# ePaper_1_54_v1_0_1.net
KiCad netlist of a schematic drawn in EAGLE
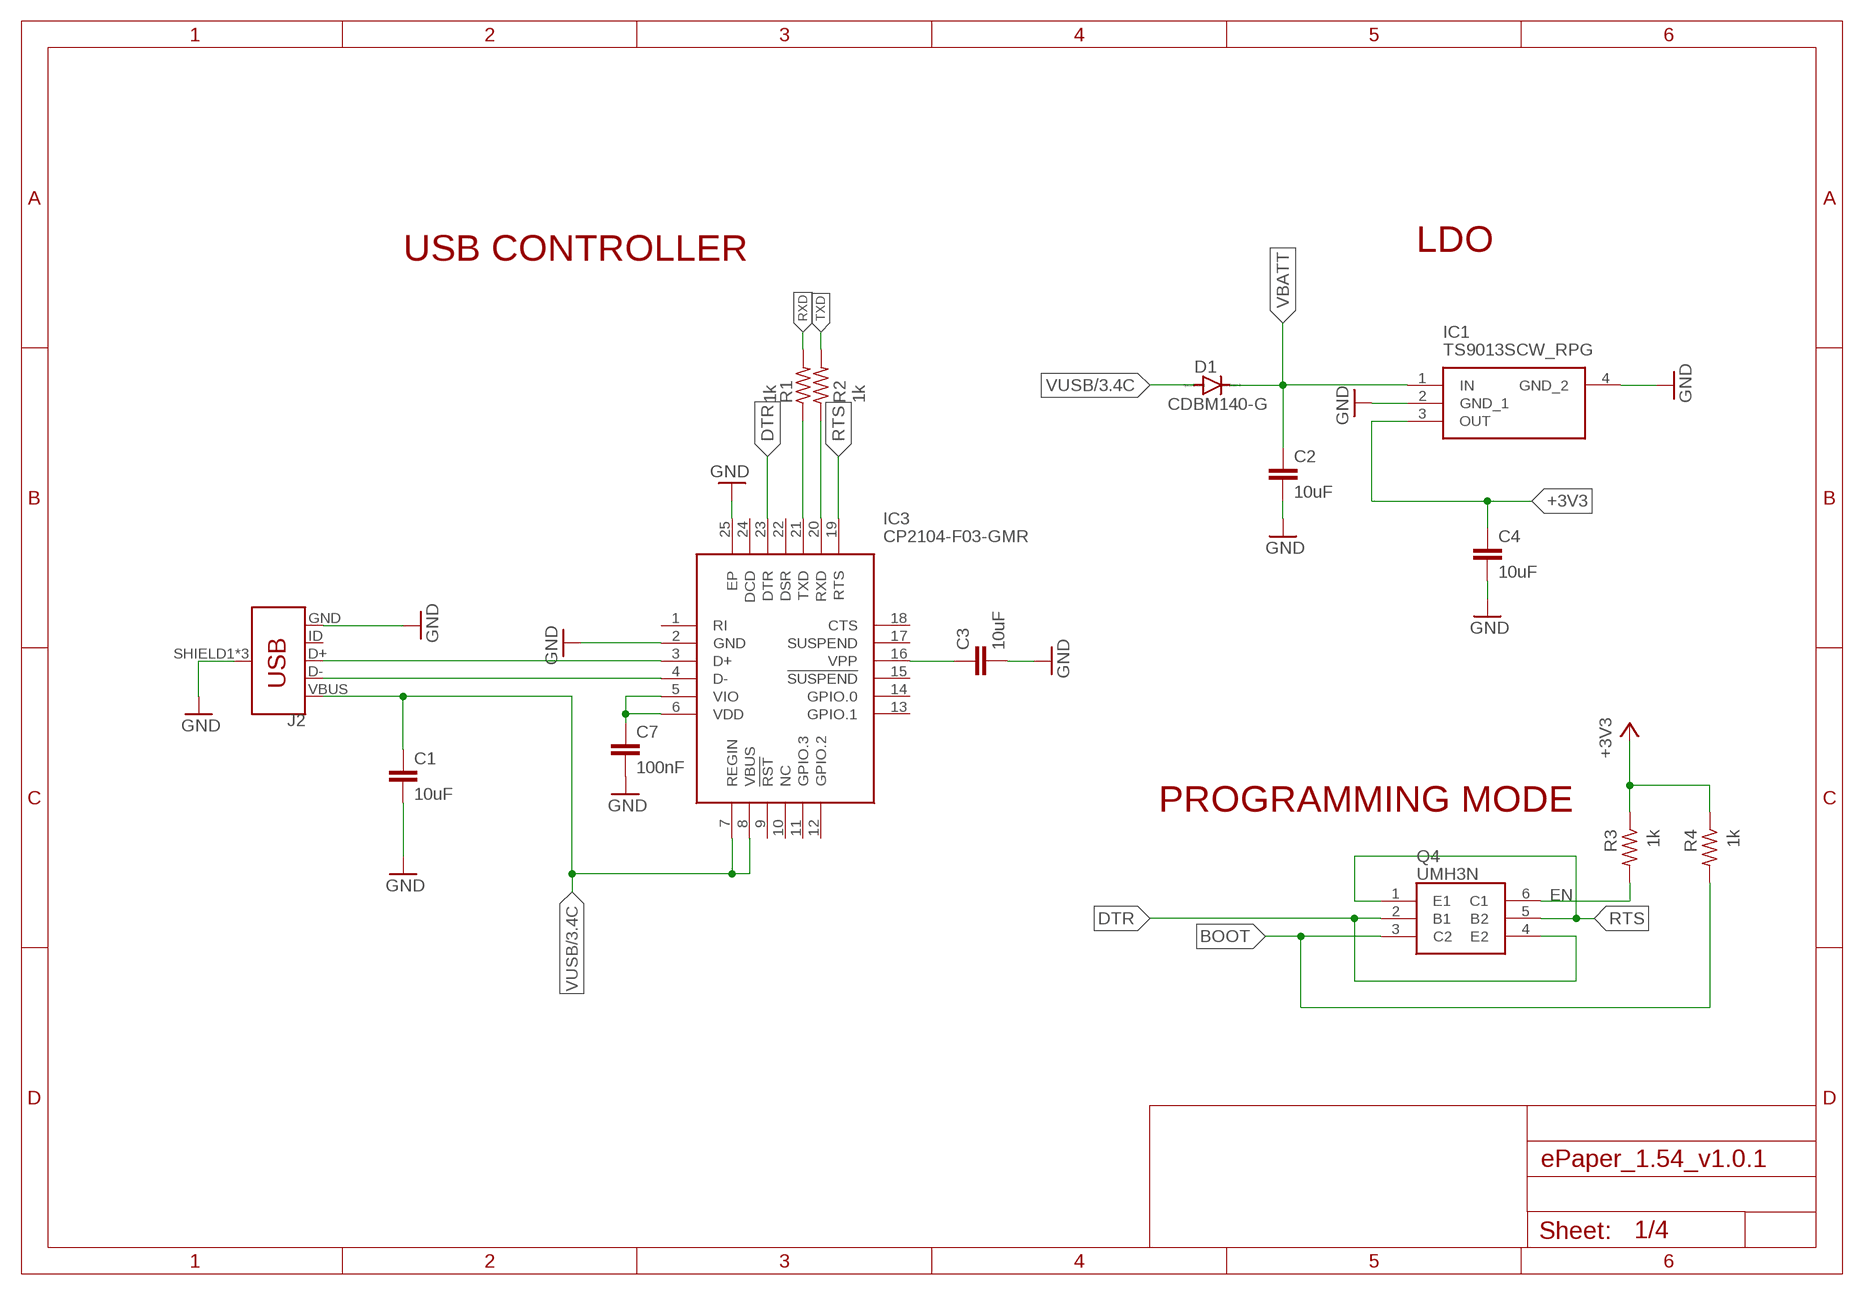
[diagram p0: schematic, sheet 1]
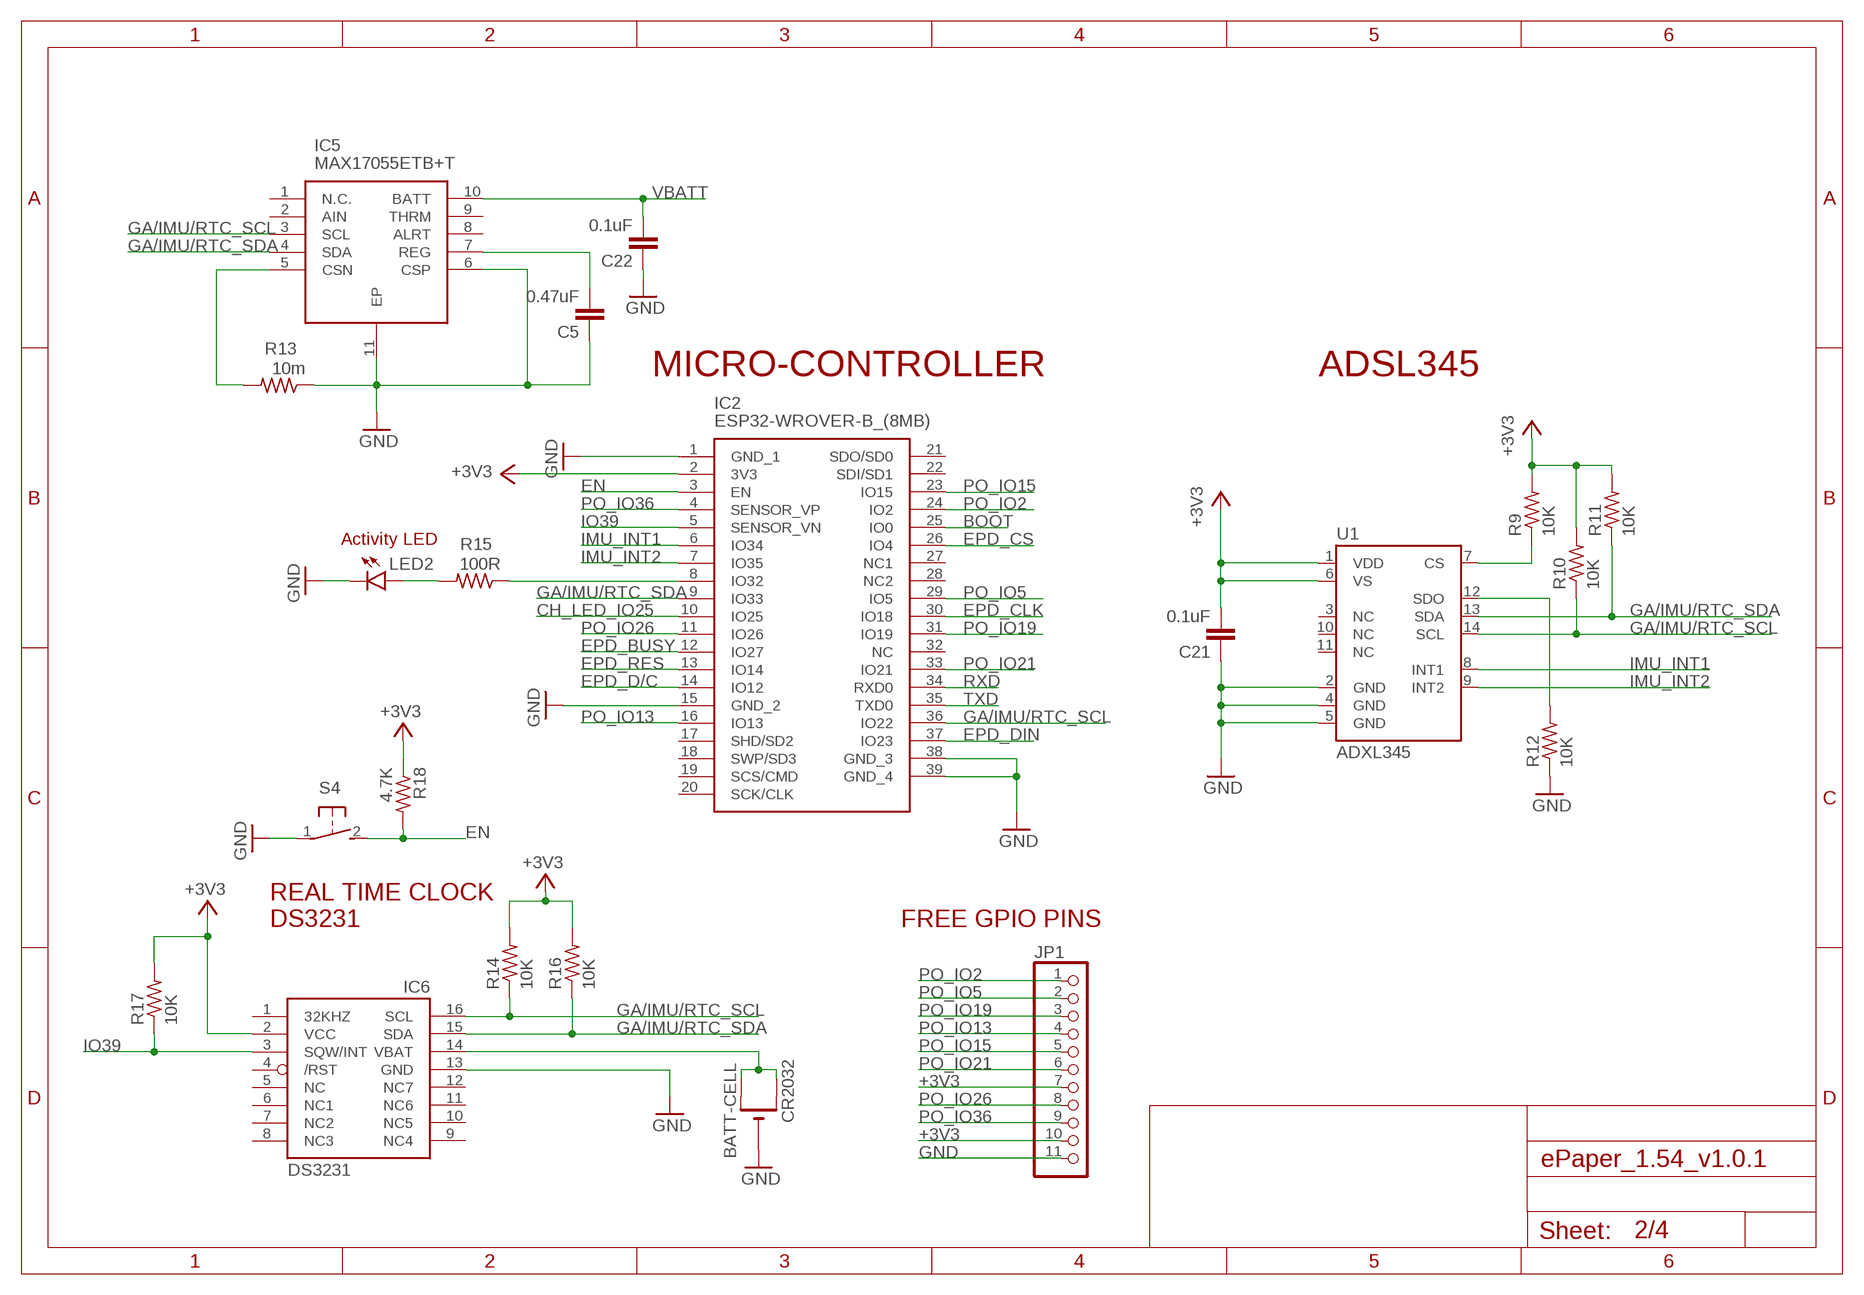
[diagram p1: schematic, sheet 2]
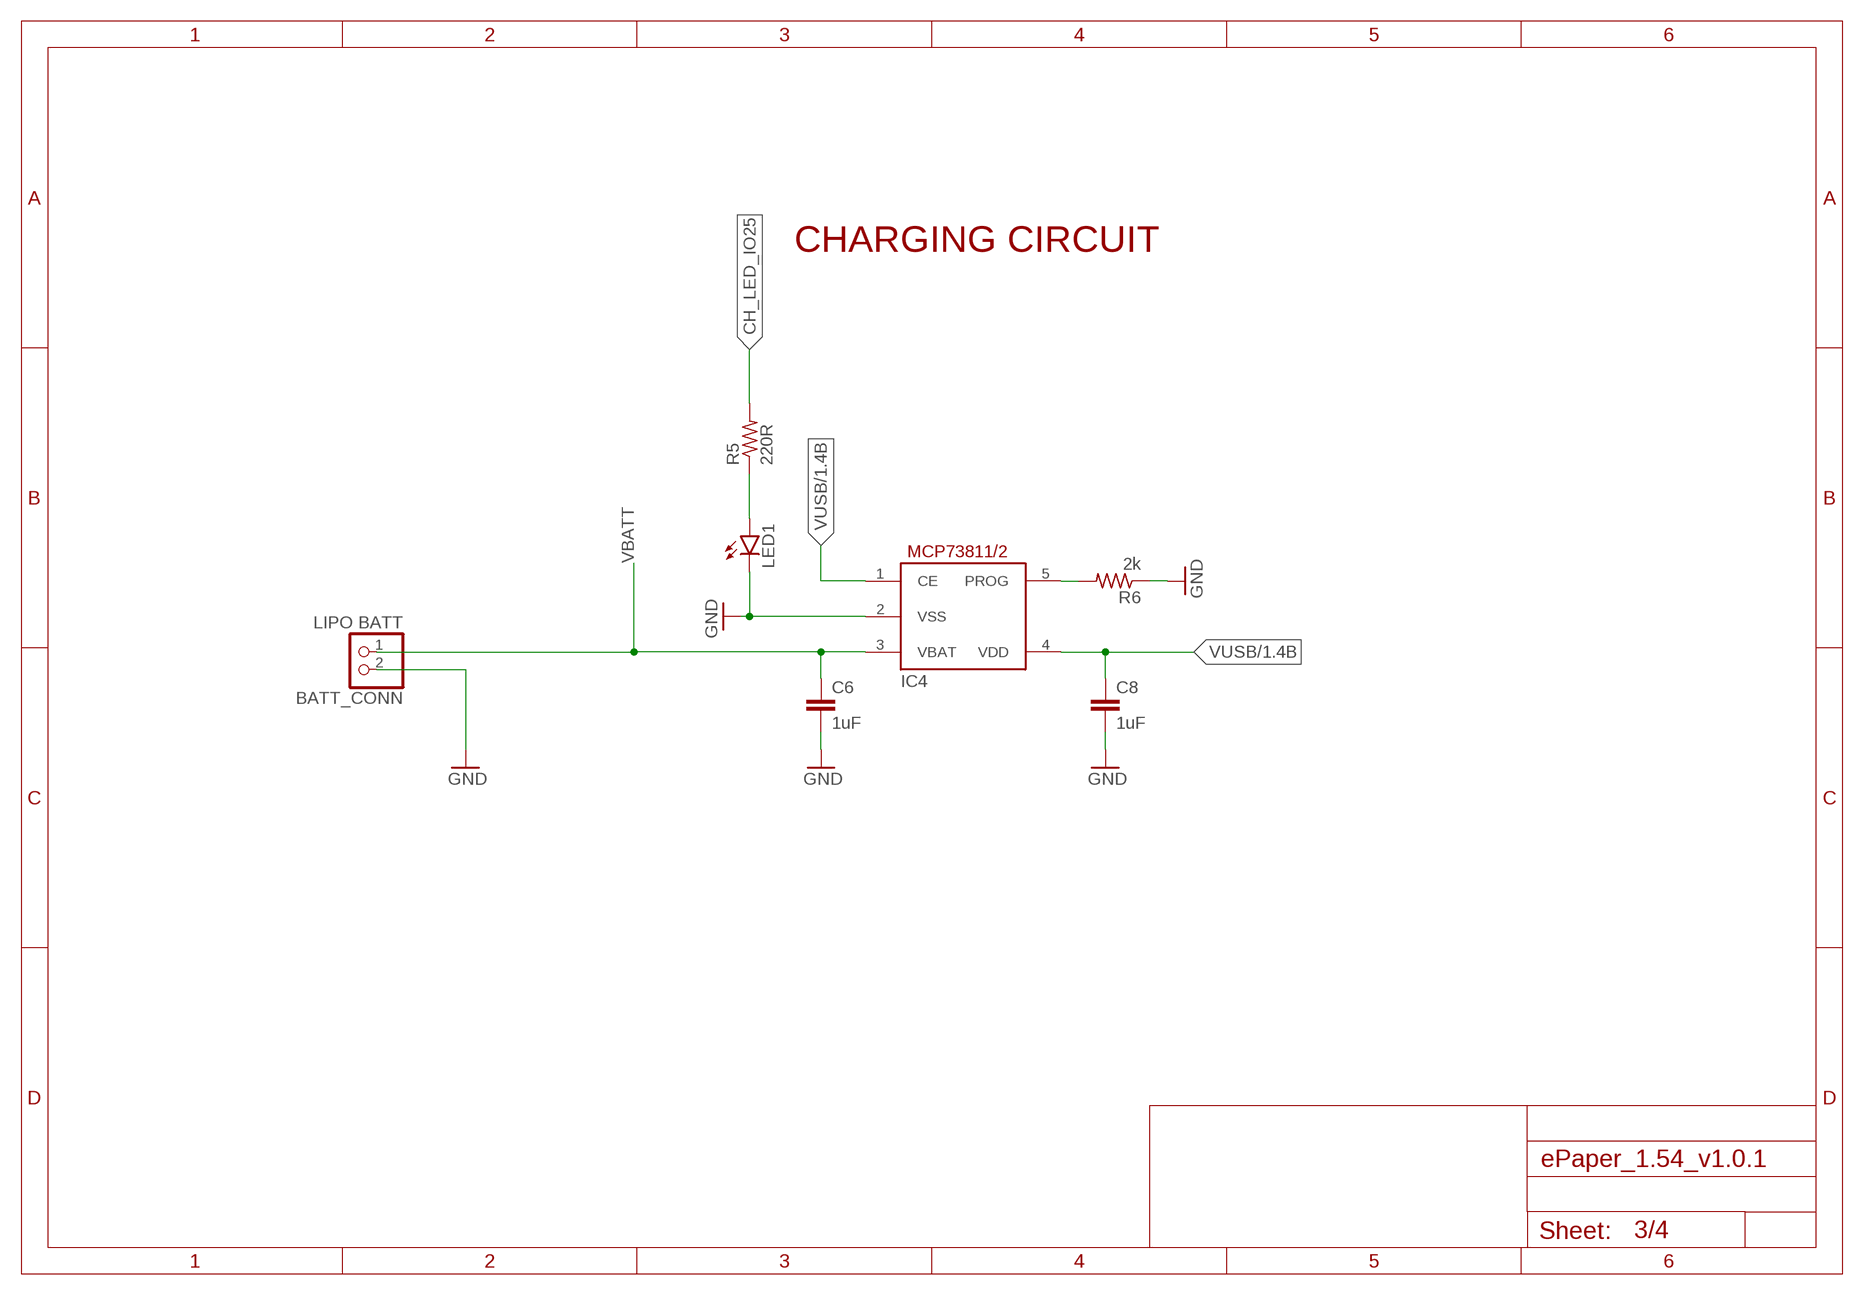
[diagram p2: schematic, sheet 3]
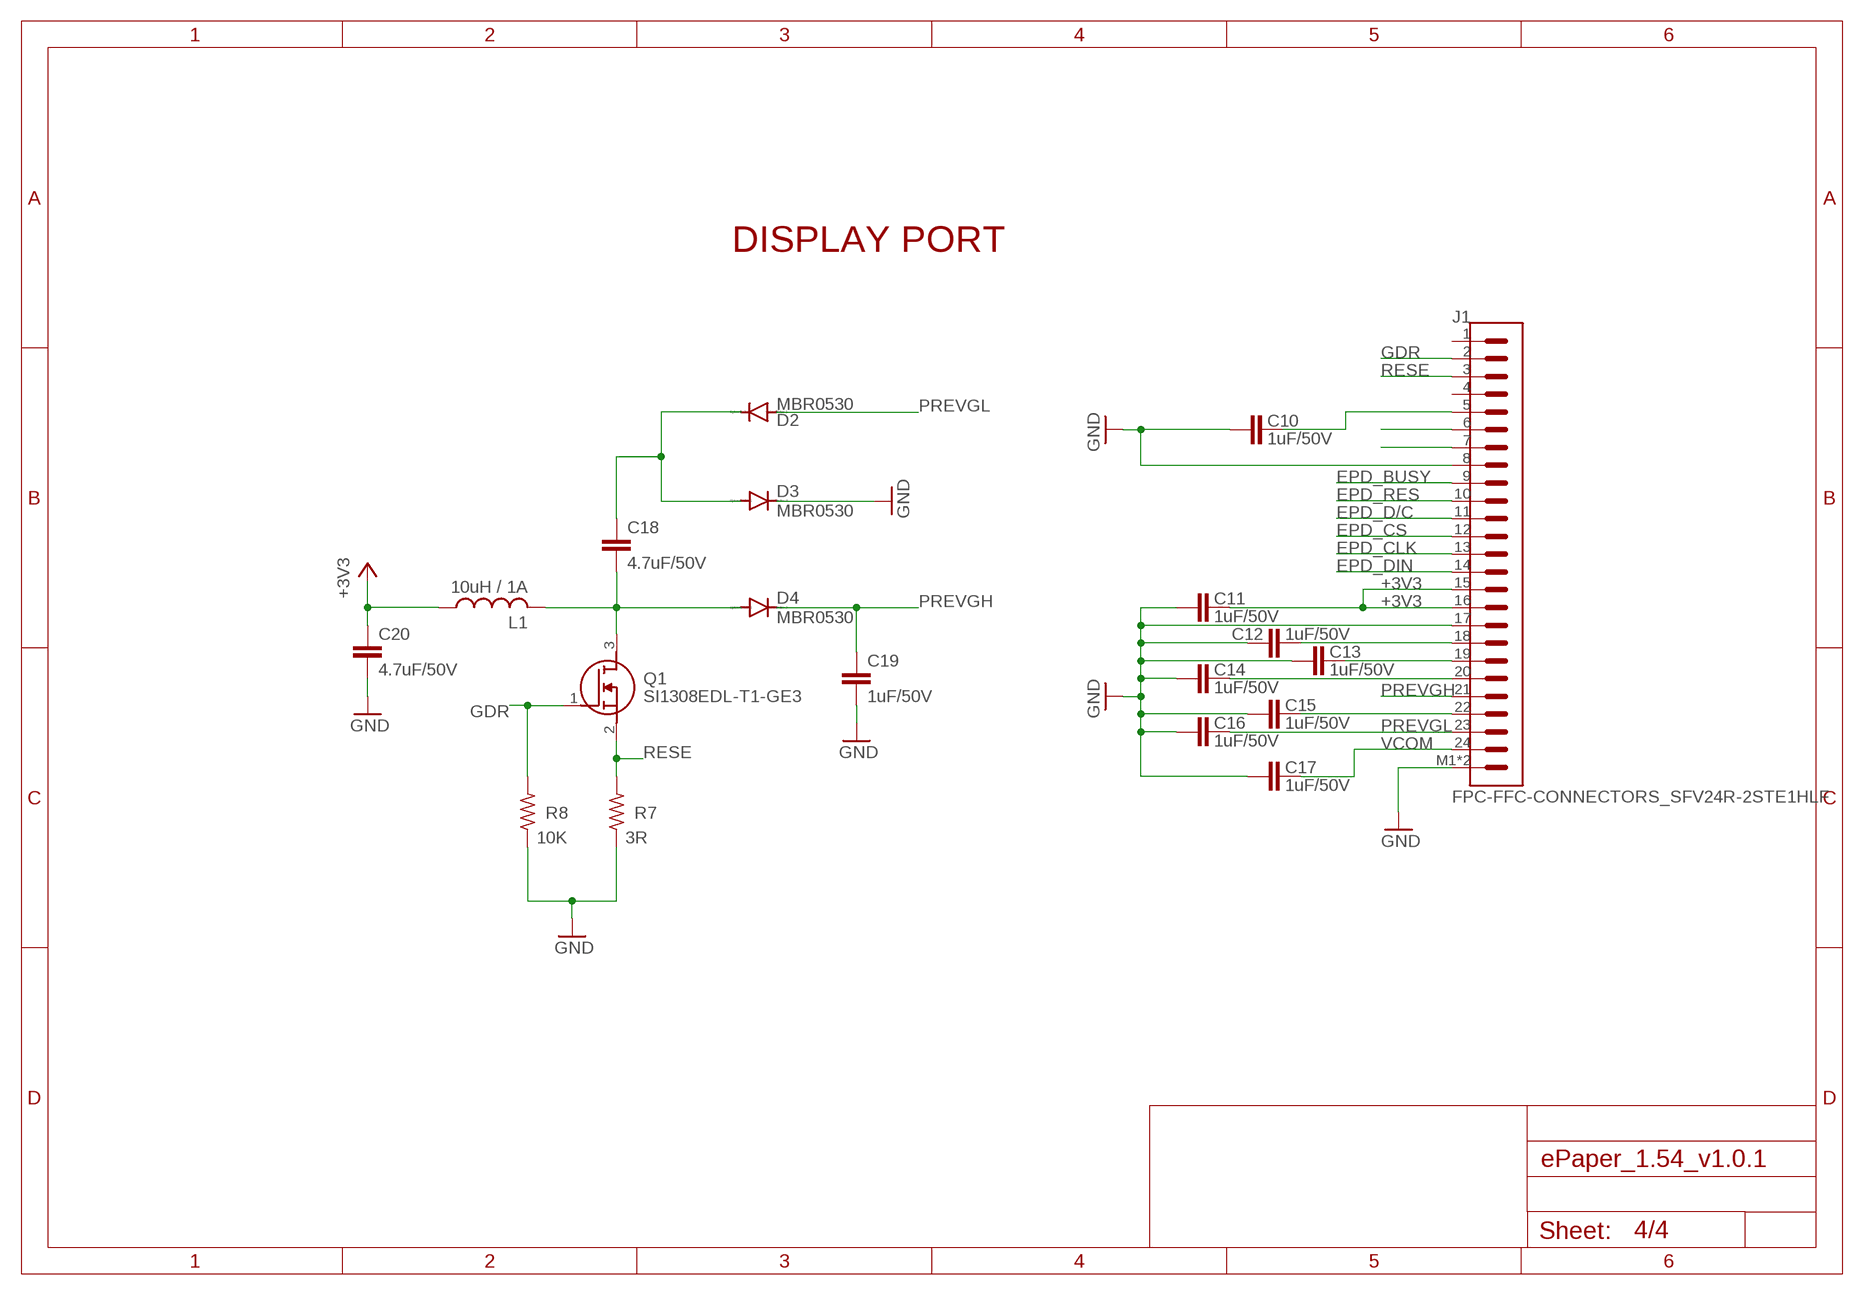
[diagram p3: schematic, sheet 4]

(export (version "E")
  (design (tool "Eeschema 10.0.6"))
  (components
    (comp (ref "BATT_CONN")
      (value "LIPO BATT")
      (footprint "eagle-import:JST-PH-2-THM-RA")
      (libsource (lib "eagle-import") (part "JST_2PIN-THM-RA"))
    )
    (comp (ref "C6")
      (value "1uF")
      (footprint "eagle-import:C0805")
      (libsource (lib "eagle-import") (part "C-EUC0805"))
    )
    (comp (ref "C8")
      (value "1uF")
      (footprint "eagle-import:C0805")
      (libsource (lib "eagle-import") (part "C-EUC0805"))
    )
    (comp (ref "IC4")
      (value "MCP73811/2")
      (footprint "eagle-import:SOT23-5L")
      (libsource (lib "eagle-import") (part "MCP73811/2"))
    )
    (comp (ref "LED1")
      (value "LEDCHIPLED_0805")
      (footprint "eagle-import:CHIPLED_0805")
      (libsource (lib "eagle-import") (part "LEDCHIPLED_0805"))
    )
    (comp (ref "R5")
      (value "220R")
      (footprint "eagle-import:R0603")
      (libsource (lib "eagle-import") (part "R-US_R0603"))
    )
    (comp (ref "R6")
      (value "2k")
      (footprint "eagle-import:R0603")
      (libsource (lib "eagle-import") (part "R-US_R0603"))
    )
    (comp (ref "C1")
      (value "10uF")
      (footprint "eagle-import:C0603")
      (libsource (lib "eagle-import") (part "C-EUC0603"))
    )
    (comp (ref "C2")
      (value "10uF")
      (footprint "eagle-import:C0603")
      (libsource (lib "eagle-import") (part "C-EUC0603"))
    )
    (comp (ref "C3")
      (value "10uF")
      (footprint "eagle-import:C0603")
      (libsource (lib "eagle-import") (part "C-EUC0603"))
    )
    (comp (ref "C4")
      (value "10uF")
      (footprint "eagle-import:C0603")
      (libsource (lib "eagle-import") (part "C-EUC0603"))
    )
    (comp (ref "C7")
      (value "100nF")
      (footprint "eagle-import:C0603")
      (libsource (lib "eagle-import") (part "C-EUC0603"))
    )
    (comp (ref "D1")
      (value "CDBM140-G")
      (footprint "eagle-import:SOD123")
      (libsource (lib "eagle-import") (part "DIODE-SOD123"))
    )
    (comp (ref "IC1")
      (value "TS9013SCW_RPG")
      (footprint "eagle-import:SOT230P700X180-4N")
      (fields (field (name "MANUFACTURER_PART_NUMBER") "TS9013SCW RPG"))
      (libsource (lib "eagle-import") (part "TS9013SCW_RPG"))
    )
    (comp (ref "IC3")
      (value "CP2104-F03-GMR")
      (footprint "eagle-import:QFN50P400X400X80-25N")
      (fields (field (name "MOUSER_PART_NUMBER") "634-CP2104-F03-GMR"))
      (libsource (lib "eagle-import") (part "CP2104-F03-GMR"))
    )
    (comp (ref "J2")
      (value "USB_MICRO-B_FEMALE-SMT")
      (footprint "eagle-import:USB-B-MICRO-SMD")
      (libsource (lib "eagle-import") (part "USB_MICRO-B_FEMALE-SMT"))
    )
    (comp (ref "Q4")
      (value "UMH3N")
      (footprint "eagle-import:SOT65P230X110-6N")
      (libsource (lib "eagle-import") (part "UMH3N"))
    )
    (comp (ref "R1")
      (value "1k")
      (footprint "eagle-import:R0603")
      (libsource (lib "eagle-import") (part "R-US_R0603"))
    )
    (comp (ref "R2")
      (value "1k")
      (footprint "eagle-import:R0603")
      (libsource (lib "eagle-import") (part "R-US_R0603"))
    )
    (comp (ref "R3")
      (value "1k")
      (footprint "eagle-import:R0603")
      (libsource (lib "eagle-import") (part "R-US_R0603"))
    )
    (comp (ref "R4")
      (value "1k")
      (footprint "eagle-import:R0603")
      (libsource (lib "eagle-import") (part "R-US_R0603"))
    )
    (comp (ref "C10")
      (value "1uF/50V")
      (footprint "eagle-import:C0805")
      (libsource (lib "eagle-import") (part "C-EUC0805"))
    )
    (comp (ref "C11")
      (value "1uF/50V")
      (footprint "eagle-import:C0805")
      (libsource (lib "eagle-import") (part "C-EUC0805"))
    )
    (comp (ref "C12")
      (value "1uF/50V")
      (footprint "eagle-import:C0805")
      (libsource (lib "eagle-import") (part "C-EUC0805"))
    )
    (comp (ref "C13")
      (value "1uF/50V")
      (footprint "eagle-import:C0805")
      (libsource (lib "eagle-import") (part "C-EUC0805"))
    )
    (comp (ref "C14")
      (value "1uF/50V")
      (footprint "eagle-import:C0805")
      (libsource (lib "eagle-import") (part "C-EUC0805"))
    )
    (comp (ref "C15")
      (value "1uF/50V")
      (footprint "eagle-import:C0805")
      (libsource (lib "eagle-import") (part "C-EUC0805"))
    )
    (comp (ref "C16")
      (value "1uF/50V")
      (footprint "eagle-import:C0805")
      (libsource (lib "eagle-import") (part "C-EUC0805"))
    )
    (comp (ref "C17")
      (value "1uF/50V")
      (footprint "eagle-import:C0805")
      (libsource (lib "eagle-import") (part "C-EUC0805"))
    )
    (comp (ref "C18")
      (value "4.7uF/50V")
      (footprint "eagle-import:C0805")
      (libsource (lib "eagle-import") (part "C-EUC0805"))
    )
    (comp (ref "C19")
      (value "1uF/50V")
      (footprint "eagle-import:C0805")
      (libsource (lib "eagle-import") (part "C-EUC0805"))
    )
    (comp (ref "C20")
      (value "4.7uF/50V")
      (footprint "eagle-import:C0805")
      (libsource (lib "eagle-import") (part "C-EUC0805"))
    )
    (comp (ref "D2")
      (value "MBR0530")
      (footprint "eagle-import:SOD123")
      (libsource (lib "eagle-import") (part "MBR0520LT"))
    )
    (comp (ref "D3")
      (value "MBR0530")
      (footprint "eagle-import:SOD123")
      (libsource (lib "eagle-import") (part "MBR0520LT"))
    )
    (comp (ref "D4")
      (value "MBR0530")
      (footprint "eagle-import:SOD123")
      (libsource (lib "eagle-import") (part "MBR0520LT"))
    )
    (comp (ref "J1")
      (value "FPC-FFC-CONNECTORS_SFV24R-2STE1HLF")
      (footprint "eagle-import:FPC-FFC-CONNECTORS_SFV24R-2STE1HLF")
      (fields
        (field (name "DIGIKEY_PARTNO") "609-4321-2-ND")
        (field (name "MANUFACTURER") "Amphenol ICC (FCI)")
        (field (name "MPN") "SFV24R-2STE1HLF")
        (field (name "CREATED_BY") "Abrar Ashraf")
      )
      (libsource (lib "eagle-import") (part "FPC-FFC-CONNECTORS_SFV24R-2STE1HLF"))
    )
    (comp (ref "L1")
      (value "10uH / 1A")
      (footprint "eagle-import:L3225P")
      (libsource (lib "eagle-import") (part "L-USL3225P"))
    )
    (comp (ref "Q1")
      (value "SI1308EDL-T1-GE3")
      (footprint "eagle-import:SOT65P210X110-3N")
      (fields
        (field (name "MANUFACTURER_PART_NUMBER") "Si1308EDL-T1-GE3")
        (field (name "MOUSER_PART_NUMBER") "78-SI1308EDL-T1-GE3")
        (field (name "RS_PART_NUMBER") "7879121P")
      )
      (libsource (lib "eagle-import") (part "SI1308EDL-T1-GE3"))
    )
    (comp (ref "R7")
      (value "3R")
      (footprint "eagle-import:R0603")
      (libsource (lib "eagle-import") (part "R-US_R0603"))
    )
    (comp (ref "R8")
      (value "10K")
      (footprint "eagle-import:R0603")
      (libsource (lib "eagle-import") (part "R-US_R0603"))
    )
    (comp (ref "BATT-CELL")
      (value "CR2032")
      (footprint "eagle-import:CR2032-SMD")
      (libsource (lib "eagle-import") (part "CR2032SMT"))
    )
    (comp (ref "C5")
      (value "0.47uF")
      (footprint "eagle-import:C0603")
      (libsource (lib "eagle-import") (part "C-EUC0603"))
    )
    (comp (ref "C21")
      (value "0.1uF")
      (footprint "eagle-import:C0603")
      (libsource (lib "eagle-import") (part "C-EUC0603"))
    )
    (comp (ref "C22")
      (value "0.1uF")
      (footprint "eagle-import:C0603")
      (libsource (lib "eagle-import") (part "C-EUC0603"))
    )
    (comp (ref "IC2")
      (value "ESP32-WROVER-B_(8MB)")
      (footprint "eagle-import:ESP32WROVERIB8MB")
      (fields
        (field (name "MANUFACTURER_PART_NUMBER") "ESP32-WROVER-B (16MB)")
        (field (name "MOUSER_PART_NUMBER") "356-ESP32-WROB(16MB)")
      )
      (libsource (lib "eagle-import") (part "ESP32-WROVER-B_(8MB)"))
    )
    (comp (ref "IC5")
      (value "MAX17055ETB+T")
      (footprint "eagle-import:SON40P250X200X80-11N")
      (fields
        (field (name "MOUSER_PART_NUMBER") "700-MAX17055ETB+T")
        (field (name "RS_PART_NUMBER") "1913808")
      )
      (libsource (lib "eagle-import") (part "MAX17055ETB+T"))
    )
    (comp (ref "IC6")
      (value "DS3231/SO")
      (footprint "eagle-import:SO16W")
      (libsource (lib "eagle-import") (part "DS3231/SO"))
    )
    (comp (ref "JP1")
      (value "PINHD-1X11_2.54-S")
      (footprint "eagle-import:1X11-S")
      (libsource (lib "eagle-import") (part "PINHD-1X11_2.54-S"))
    )
    (comp (ref "LED2")
      (value "LEDCHIPLED_0805")
      (footprint "eagle-import:CHIPLED_0805")
      (libsource (lib "eagle-import") (part "LEDCHIPLED_0805"))
    )
    (comp (ref "R9")
      (value "10K")
      (footprint "eagle-import:R0603")
      (libsource (lib "eagle-import") (part "R-US_R0603"))
    )
    (comp (ref "R10")
      (value "10K")
      (footprint "eagle-import:R0603")
      (libsource (lib "eagle-import") (part "R-US_R0603"))
    )
    (comp (ref "R11")
      (value "10K")
      (footprint "eagle-import:R0603")
      (libsource (lib "eagle-import") (part "R-US_R0603"))
    )
    (comp (ref "R12")
      (value "10K")
      (footprint "eagle-import:R0603")
      (libsource (lib "eagle-import") (part "R-US_R0603"))
    )
    (comp (ref "R13")
      (value "10m")
      (footprint "eagle-import:R0603")
      (libsource (lib "eagle-import") (part "R-US_R0603"))
    )
    (comp (ref "R14")
      (value "10K")
      (footprint "eagle-import:R0603")
      (libsource (lib "eagle-import") (part "R-US_R0603"))
    )
    (comp (ref "R15")
      (value "100R")
      (footprint "eagle-import:R0603")
      (libsource (lib "eagle-import") (part "R-US_R0603"))
    )
    (comp (ref "R16")
      (value "10K")
      (footprint "eagle-import:R0603")
      (libsource (lib "eagle-import") (part "R-US_R0603"))
    )
    (comp (ref "R17")
      (value "10K")
      (footprint "eagle-import:R0603")
      (libsource (lib "eagle-import") (part "R-US_R0603"))
    )
    (comp (ref "R18")
      (value "4.7K")
      (footprint "eagle-import:R0603")
      (libsource (lib "eagle-import") (part "R-US_R0603"))
    )
    (comp (ref "S4")
      (value "31-XX")
      (footprint "eagle-import:B3F-31XX")
      (fields (field (name "MPN") "B3F-3100"))
      (libsource (lib "eagle-import") (part "31-XX"))
    )
    (comp (ref "U1")
      (value "ADXL345")
      (footprint "eagle-import:LGA14")
      (libsource (lib "eagle-import") (part "ADXL345"))
    )
  )
  (nets
    (net (code "1") (name "+3V3") (class "Default")
      (node (ref "C11") (pin "2") (pinfunction "2_2") (pintype "passive"))
      (node (ref "C20") (pin "2") (pinfunction "2_2") (pintype "passive"))
      (node (ref "C21") (pin "2") (pinfunction "2_2") (pintype "passive"))
      (node (ref "C4") (pin "1") (pinfunction "1_1") (pintype "passive"))
      (node (ref "IC1") (pin "3") (pinfunction "OUT_3") (pintype "output"))
      (node (ref "IC2") (pin "2") (pinfunction "3V3_2") (pintype "bidirectional"))
      (node (ref "IC6") (pin "2") (pinfunction "VCC_2") (pintype "power_in"))
      (node (ref "J1") (pin "15") (pinfunction "15_15") (pintype "passive"))
      (node (ref "J1") (pin "16") (pinfunction "16_16") (pintype "passive"))
      (node (ref "JP1") (pin "10") (pinfunction "10_10") (pintype "passive"))
      (node (ref "JP1") (pin "7") (pinfunction "7_7") (pintype "passive"))
      (node (ref "L1") (pin "1") (pinfunction "1_1") (pintype "passive"))
      (node (ref "R10") (pin "2") (pinfunction "2_2") (pintype "passive"))
      (node (ref "R11") (pin "2") (pinfunction "2_2") (pintype "passive"))
      (node (ref "R14") (pin "2") (pinfunction "2_2") (pintype "passive"))
      (node (ref "R16") (pin "2") (pinfunction "2_2") (pintype "passive"))
      (node (ref "R17") (pin "2") (pinfunction "2_2") (pintype "passive"))
      (node (ref "R18") (pin "1") (pinfunction "1_1") (pintype "passive"))
      (node (ref "R3") (pin "1") (pinfunction "1_1") (pintype "passive"))
      (node (ref "R4") (pin "1") (pinfunction "1_1") (pintype "passive"))
      (node (ref "R9") (pin "2") (pinfunction "2_2") (pintype "passive"))
      (node (ref "U1") (pin "1") (pinfunction "VDD_1") (pintype "bidirectional"))
      (node (ref "U1") (pin "6") (pinfunction "VS_6") (pintype "bidirectional"))
    )
    (net (code "2") (name "BOOT") (class "Default")
      (node (ref "IC2") (pin "25") (pinfunction "IO0_25") (pintype "bidirectional"))
      (node (ref "Q4") (pin "3") (pinfunction "C2_3") (pintype "bidirectional"))
      (node (ref "R4") (pin "2") (pinfunction "2_2") (pintype "passive"))
    )
    (net (code "3") (name "CH_LED_IO25") (class "Default")
      (node (ref "IC2") (pin "10") (pinfunction "IO25_10") (pintype "bidirectional"))
      (node (ref "R5") (pin "2") (pinfunction "2_2") (pintype "passive"))
    )
    (net (code "4") (name "DTR") (class "Default")
      (node (ref "IC3") (pin "23") (pinfunction "DTR_23") (pintype "bidirectional"))
      (node (ref "Q4") (pin "2") (pinfunction "B1_2") (pintype "bidirectional"))
      (node (ref "Q4") (pin "4") (pinfunction "E2_4") (pintype "bidirectional"))
    )
    (net (code "5") (name "EN") (class "Default")
      (node (ref "IC2") (pin "3") (pinfunction "EN_3") (pintype "bidirectional"))
      (node (ref "Q4") (pin "6") (pinfunction "C1_6") (pintype "bidirectional"))
      (node (ref "R18") (pin "2") (pinfunction "2_2") (pintype "passive"))
      (node (ref "R3") (pin "2") (pinfunction "2_2") (pintype "passive"))
      (node (ref "S4") (pin "2") (pinfunction "S_2") (pintype "passive"))
    )
    (net (code "6") (name "EPD_BUSY") (class "Default")
      (node (ref "IC2") (pin "12") (pinfunction "IO27_12") (pintype "bidirectional"))
      (node (ref "J1") (pin "9") (pinfunction "9_9") (pintype "passive"))
    )
    (net (code "7") (name "EPD_CLK") (class "Default")
      (node (ref "IC2") (pin "30") (pinfunction "IO18_30") (pintype "bidirectional"))
      (node (ref "J1") (pin "13") (pinfunction "13_13") (pintype "passive"))
    )
    (net (code "8") (name "EPD_CS") (class "Default")
      (node (ref "IC2") (pin "26") (pinfunction "IO4_26") (pintype "bidirectional"))
      (node (ref "J1") (pin "12") (pinfunction "12_12") (pintype "passive"))
    )
    (net (code "9") (name "EPD_DIN") (class "Default")
      (node (ref "IC2") (pin "37") (pinfunction "IO23_37") (pintype "bidirectional"))
      (node (ref "J1") (pin "14") (pinfunction "14_14") (pintype "passive"))
    )
    (net (code "10") (name "EPD_D{slash}C") (class "Default")
      (node (ref "IC2") (pin "14") (pinfunction "IO12_14") (pintype "bidirectional"))
      (node (ref "J1") (pin "11") (pinfunction "11_11") (pintype "passive"))
    )
    (net (code "11") (name "EPD_RES") (class "Default")
      (node (ref "IC2") (pin "13") (pinfunction "IO14_13") (pintype "bidirectional"))
      (node (ref "J1") (pin "10") (pinfunction "10_10") (pintype "passive"))
    )
    (net (code "12") (name "GA{slash}IMU{slash}RTC_SCL") (class "Default")
      (node (ref "IC2") (pin "36") (pinfunction "IO22_36") (pintype "bidirectional"))
      (node (ref "IC5") (pin "3") (pinfunction "SCL_3") (pintype "bidirectional"))
      (node (ref "IC6") (pin "16") (pinfunction "SCL_16") (pintype "bidirectional"))
      (node (ref "R10") (pin "1") (pinfunction "1_1") (pintype "passive"))
      (node (ref "R14") (pin "1") (pinfunction "1_1") (pintype "passive"))
      (node (ref "U1") (pin "14") (pinfunction "SCL_14") (pintype "bidirectional"))
    )
    (net (code "13") (name "GA{slash}IMU{slash}RTC_SDA") (class "Default")
      (node (ref "IC2") (pin "9") (pinfunction "IO33_9") (pintype "bidirectional"))
      (node (ref "IC5") (pin "4") (pinfunction "SDA_4") (pintype "bidirectional"))
      (node (ref "IC6") (pin "15") (pinfunction "SDA_15") (pintype "bidirectional"))
      (node (ref "R11") (pin "1") (pinfunction "1_1") (pintype "passive"))
      (node (ref "R16") (pin "1") (pinfunction "1_1") (pintype "passive"))
      (node (ref "U1") (pin "13") (pinfunction "SDA_13") (pintype "bidirectional"))
    )
    (net (code "14") (name "GDR") (class "Default")
      (node (ref "J1") (pin "2") (pinfunction "2_2") (pintype "passive"))
      (node (ref "Q1") (pin "1") (pinfunction "G_1") (pintype "input"))
      (node (ref "R8") (pin "2") (pinfunction "2_2") (pintype "passive"))
    )
    (net (code "15") (name "GND") (class "Default")
      (node (ref "BATT-CELL") (pin "-") (pinfunction "-_-") (pintype "passive"))
      (node (ref "BATT_CONN") (pin "2") (pinfunction "1_2") (pintype "passive"))
      (node (ref "C1") (pin "2") (pinfunction "2_2") (pintype "passive"))
      (node (ref "C10") (pin "1") (pinfunction "1_1") (pintype "passive"))
      (node (ref "C11") (pin "1") (pinfunction "1_1") (pintype "passive"))
      (node (ref "C12") (pin "1") (pinfunction "1_1") (pintype "passive"))
      (node (ref "C13") (pin "1") (pinfunction "1_1") (pintype "passive"))
      (node (ref "C14") (pin "1") (pinfunction "1_1") (pintype "passive"))
      (node (ref "C15") (pin "1") (pinfunction "1_1") (pintype "passive"))
      (node (ref "C16") (pin "1") (pinfunction "1_1") (pintype "passive"))
      (node (ref "C17") (pin "1") (pinfunction "1_1") (pintype "passive"))
      (node (ref "C19") (pin "1") (pinfunction "1_1") (pintype "passive"))
      (node (ref "C2") (pin "2") (pinfunction "2_2") (pintype "passive"))
      (node (ref "C20") (pin "1") (pinfunction "1_1") (pintype "passive"))
      (node (ref "C21") (pin "1") (pinfunction "1_1") (pintype "passive"))
      (node (ref "C22") (pin "1") (pinfunction "1_1") (pintype "passive"))
      (node (ref "C3") (pin "2") (pinfunction "2_2") (pintype "passive"))
      (node (ref "C4") (pin "2") (pinfunction "2_2") (pintype "passive"))
      (node (ref "C5") (pin "1") (pinfunction "1_1") (pintype "passive"))
      (node (ref "C6") (pin "2") (pinfunction "2_2") (pintype "passive"))
      (node (ref "C7") (pin "2") (pinfunction "2_2") (pintype "passive"))
      (node (ref "C8") (pin "2") (pinfunction "2_2") (pintype "passive"))
      (node (ref "D3") (pin "C") (pinfunction "C_C") (pintype "passive"))
      (node (ref "IC1") (pin "2") (pinfunction "GND_1_2") (pintype "power_in"))
      (node (ref "IC1") (pin "4") (pinfunction "GND_2_4") (pintype "power_in"))
      (node (ref "IC2") (pin "1") (pinfunction "GND_1_1") (pintype "bidirectional"))
      (node (ref "IC2") (pin "15") (pinfunction "GND_2_15") (pintype "bidirectional"))
      (node (ref "IC2") (pin "38") (pinfunction "GND_3_38") (pintype "bidirectional"))
      (node (ref "IC2") (pin "39") (pinfunction "GND_4_39") (pintype "bidirectional"))
      (node (ref "IC3") (pin "2") (pinfunction "GND_2") (pintype "bidirectional"))
      (node (ref "IC3") (pin "25") (pinfunction "EP_25") (pintype "bidirectional"))
      (node (ref "IC4") (pin "2") (pinfunction "VSS_2") (pintype "power_in"))
      (node (ref "IC5") (pin "11") (pinfunction "EP_11") (pintype "bidirectional"))
      (node (ref "IC5") (pin "6") (pinfunction "CSP_6") (pintype "bidirectional"))
      (node (ref "IC6") (pin "13") (pinfunction "GND_13") (pintype "power_in"))
      (node (ref "J1") (pin "17") (pinfunction "17_17") (pintype "passive"))
      (node (ref "J1") (pin "8") (pinfunction "8_8") (pintype "passive"))
      (node (ref "J1") (pin "M1") (pinfunction "SHIELD_M1") (pintype "power_in"))
      (node (ref "J1") (pin "M2") (pinfunction "SHIELD_M2") (pintype "power_in"))
      (node (ref "J2") (pin "GND") (pinfunction "GND_GND") (pintype "power_in"))
      (node (ref "J2") (pin "SHIELD1") (pinfunction "SHIELD_SHIELD1") (pintype "bidirectional"))
      (node (ref "J2") (pin "SHIELD2") (pinfunction "SHIELD_SHIELD2") (pintype "bidirectional"))
      (node (ref "J2") (pin "SHIELD3") (pinfunction "SHIELD_SHIELD3") (pintype "bidirectional"))
      (node (ref "JP1") (pin "11") (pinfunction "11_11") (pintype "passive"))
      (node (ref "LED1") (pin "C") (pinfunction "C_C") (pintype "passive"))
      (node (ref "LED2") (pin "C") (pinfunction "C_C") (pintype "passive"))
      (node (ref "R12") (pin "1") (pinfunction "1_1") (pintype "passive"))
      (node (ref "R13") (pin "1") (pinfunction "1_1") (pintype "passive"))
      (node (ref "R6") (pin "1") (pinfunction "1_1") (pintype "passive"))
      (node (ref "R7") (pin "1") (pinfunction "1_1") (pintype "passive"))
      (node (ref "R8") (pin "1") (pinfunction "1_1") (pintype "passive"))
      (node (ref "S4") (pin "1") (pinfunction "P_1") (pintype "passive"))
      (node (ref "U1") (pin "2") (pinfunction "GND_2") (pintype "bidirectional"))
      (node (ref "U1") (pin "4") (pinfunction "GND_4") (pintype "bidirectional"))
      (node (ref "U1") (pin "5") (pinfunction "GND_5") (pintype "bidirectional"))
    )
    (net (code "16") (name "IMU_INT1") (class "Default")
      (node (ref "IC2") (pin "6") (pinfunction "IO34_6") (pintype "bidirectional"))
      (node (ref "U1") (pin "8") (pinfunction "INT1_8") (pintype "bidirectional"))
    )
    (net (code "17") (name "IMU_INT2") (class "Default")
      (node (ref "IC2") (pin "7") (pinfunction "IO35_7") (pintype "bidirectional"))
      (node (ref "U1") (pin "9") (pinfunction "INT2_9") (pintype "bidirectional"))
    )
    (net (code "18") (name "IO39") (class "Default")
      (node (ref "IC2") (pin "5") (pinfunction "SENSOR_VN_5") (pintype "bidirectional"))
      (node (ref "IC6") (pin "3") (pinfunction "SQW/INT_3") (pintype "output"))
      (node (ref "R17") (pin "1") (pinfunction "1_1") (pintype "passive"))
    )
    (net (code "19") (name "Net-(BATT-CELL-+)") (class "Default")
      (node (ref "BATT-CELL") (pin "+$1") (pinfunction "+_+$1") (pintype "passive"))
      (node (ref "BATT-CELL") (pin "+$2") (pinfunction "+1_+$2") (pintype "passive"))
      (node (ref "IC6") (pin "14") (pinfunction "VBAT_14") (pintype "power_in"))
    )
    (net (code "20") (name "Net-(C10-Pad2)") (class "Default")
      (node (ref "C10") (pin "2") (pinfunction "2_2") (pintype "passive"))
      (node (ref "J1") (pin "5") (pinfunction "5_5") (pintype "passive"))
    )
    (net (code "21") (name "Net-(C12-Pad2)") (class "Default")
      (node (ref "C12") (pin "2") (pinfunction "2_2") (pintype "passive"))
      (node (ref "J1") (pin "18") (pinfunction "18_18") (pintype "passive"))
    )
    (net (code "22") (name "Net-(C13-Pad2)") (class "Default")
      (node (ref "C13") (pin "2") (pinfunction "2_2") (pintype "passive"))
      (node (ref "J1") (pin "19") (pinfunction "19_19") (pintype "passive"))
    )
    (net (code "23") (name "Net-(C14-Pad2)") (class "Default")
      (node (ref "C14") (pin "2") (pinfunction "2_2") (pintype "passive"))
      (node (ref "J1") (pin "20") (pinfunction "20_20") (pintype "passive"))
    )
    (net (code "24") (name "Net-(C15-Pad2)") (class "Default")
      (node (ref "C15") (pin "2") (pinfunction "2_2") (pintype "passive"))
      (node (ref "J1") (pin "22") (pinfunction "22_22") (pintype "passive"))
    )
    (net (code "25") (name "Net-(C18-Pad2)") (class "Default")
      (node (ref "C18") (pin "2") (pinfunction "2_2") (pintype "passive"))
      (node (ref "D2") (pin "C") (pinfunction "C_C") (pintype "passive"))
      (node (ref "D3") (pin "A") (pinfunction "A_A") (pintype "passive"))
    )
    (net (code "26") (name "Net-(IC2-IO32)") (class "Default")
      (node (ref "IC2") (pin "8") (pinfunction "IO32_8") (pintype "bidirectional"))
      (node (ref "R15") (pin "1") (pinfunction "1_1") (pintype "passive"))
    )
    (net (code "27") (name "Net-(IC3-D+)") (class "Default")
      (node (ref "IC3") (pin "3") (pinfunction "D+_3") (pintype "bidirectional"))
      (node (ref "J2") (pin "D+") (pinfunction "D+_D+") (pintype "bidirectional"))
    )
    (net (code "28") (name "Net-(IC3-D-)") (class "Default")
      (node (ref "IC3") (pin "4") (pinfunction "D-_4") (pintype "bidirectional"))
      (node (ref "J2") (pin "D-") (pinfunction "D-_D-") (pintype "bidirectional"))
    )
    (net (code "29") (name "Net-(IC3-RXD)") (class "Default")
      (node (ref "IC3") (pin "20") (pinfunction "RXD_20") (pintype "bidirectional"))
      (node (ref "R2") (pin "1") (pinfunction "1_1") (pintype "passive"))
    )
    (net (code "30") (name "Net-(IC3-TXD)") (class "Default")
      (node (ref "IC3") (pin "21") (pinfunction "TXD_21") (pintype "bidirectional"))
      (node (ref "R1") (pin "1") (pinfunction "1_1") (pintype "passive"))
    )
    (net (code "31") (name "Net-(IC3-VDD)") (class "Default")
      (node (ref "C7") (pin "1") (pinfunction "1_1") (pintype "passive"))
      (node (ref "IC3") (pin "5") (pinfunction "VIO_5") (pintype "bidirectional"))
      (node (ref "IC3") (pin "6") (pinfunction "VDD_6") (pintype "bidirectional"))
    )
    (net (code "32") (name "Net-(IC3-VPP)") (class "Default")
      (node (ref "C3") (pin "1") (pinfunction "1_1") (pintype "passive"))
      (node (ref "IC3") (pin "16") (pinfunction "VPP_16") (pintype "bidirectional"))
    )
    (net (code "33") (name "Net-(IC4-PROG)") (class "Default")
      (node (ref "IC4") (pin "5") (pinfunction "PROG_5") (pintype "input"))
      (node (ref "R6") (pin "2") (pinfunction "2_2") (pintype "passive"))
    )
    (net (code "34") (name "Net-(IC5-CSN)") (class "Default")
      (node (ref "IC5") (pin "5") (pinfunction "CSN_5") (pintype "bidirectional"))
      (node (ref "R13") (pin "2") (pinfunction "2_2") (pintype "passive"))
    )
    (net (code "35") (name "Net-(IC5-REG)") (class "Default")
      (node (ref "C5") (pin "2") (pinfunction "2_2") (pintype "passive"))
      (node (ref "IC5") (pin "7") (pinfunction "REG_7") (pintype "bidirectional"))
    )
    (net (code "36") (name "Net-(LED1-PadA)") (class "Default")
      (node (ref "LED1") (pin "A") (pinfunction "A_A") (pintype "passive"))
      (node (ref "R5") (pin "1") (pinfunction "1_1") (pintype "passive"))
    )
    (net (code "37") (name "Net-(LED2-PadA)") (class "Default")
      (node (ref "LED2") (pin "A") (pinfunction "A_A") (pintype "passive"))
      (node (ref "R15") (pin "2") (pinfunction "2_2") (pintype "passive"))
    )
    (net (code "38") (name "Net-(Q1-D)") (class "Default")
      (node (ref "C18") (pin "1") (pinfunction "1_1") (pintype "passive"))
      (node (ref "D4") (pin "A") (pinfunction "A_A") (pintype "passive"))
      (node (ref "L1") (pin "2") (pinfunction "2_2") (pintype "passive"))
      (node (ref "Q1") (pin "3") (pinfunction "D_3") (pintype "bidirectional"))
    )
    (net (code "39") (name "Net-(U1-CS)") (class "Default")
      (node (ref "R9") (pin "1") (pinfunction "1_1") (pintype "passive"))
      (node (ref "U1") (pin "7") (pinfunction "CS_7") (pintype "bidirectional"))
    )
    (net (code "40") (name "Net-(U1-SDO)") (class "Default")
      (node (ref "R12") (pin "2") (pinfunction "2_2") (pintype "passive"))
      (node (ref "U1") (pin "12") (pinfunction "SDO_12") (pintype "bidirectional"))
    )
    (net (code "41") (name "PO_IO2") (class "Default")
      (node (ref "IC2") (pin "24") (pinfunction "IO2_24") (pintype "bidirectional"))
      (node (ref "JP1") (pin "1") (pinfunction "1_1") (pintype "passive"))
    )
    (net (code "42") (name "PO_IO5") (class "Default")
      (node (ref "IC2") (pin "29") (pinfunction "IO5_29") (pintype "bidirectional"))
      (node (ref "JP1") (pin "2") (pinfunction "2_2") (pintype "passive"))
    )
    (net (code "43") (name "PO_IO13") (class "Default")
      (node (ref "IC2") (pin "16") (pinfunction "IO13_16") (pintype "bidirectional"))
      (node (ref "JP1") (pin "4") (pinfunction "4_4") (pintype "passive"))
    )
    (net (code "44") (name "PO_IO15") (class "Default")
      (node (ref "IC2") (pin "23") (pinfunction "IO15_23") (pintype "bidirectional"))
      (node (ref "JP1") (pin "5") (pinfunction "5_5") (pintype "passive"))
    )
    (net (code "45") (name "PO_IO19") (class "Default")
      (node (ref "IC2") (pin "31") (pinfunction "IO19_31") (pintype "bidirectional"))
      (node (ref "JP1") (pin "3") (pinfunction "3_3") (pintype "passive"))
    )
    (net (code "46") (name "PO_IO21") (class "Default")
      (node (ref "IC2") (pin "33") (pinfunction "IO21_33") (pintype "bidirectional"))
      (node (ref "JP1") (pin "6") (pinfunction "6_6") (pintype "passive"))
    )
    (net (code "47") (name "PO_IO26") (class "Default")
      (node (ref "IC2") (pin "11") (pinfunction "IO26_11") (pintype "bidirectional"))
      (node (ref "JP1") (pin "8") (pinfunction "8_8") (pintype "passive"))
    )
    (net (code "48") (name "PO_IO36") (class "Default")
      (node (ref "IC2") (pin "4") (pinfunction "SENSOR_VP_4") (pintype "bidirectional"))
      (node (ref "JP1") (pin "9") (pinfunction "9_9") (pintype "passive"))
    )
    (net (code "49") (name "PREVGH") (class "Default")
      (node (ref "C19") (pin "2") (pinfunction "2_2") (pintype "passive"))
      (node (ref "D4") (pin "C") (pinfunction "C_C") (pintype "passive"))
      (node (ref "J1") (pin "21") (pinfunction "21_21") (pintype "passive"))
    )
    (net (code "50") (name "PREVGL") (class "Default")
      (node (ref "C16") (pin "2") (pinfunction "2_2") (pintype "passive"))
      (node (ref "D2") (pin "A") (pinfunction "A_A") (pintype "passive"))
      (node (ref "J1") (pin "23") (pinfunction "23_23") (pintype "passive"))
    )
    (net (code "51") (name "RESE") (class "Default")
      (node (ref "J1") (pin "3") (pinfunction "3_3") (pintype "passive"))
      (node (ref "Q1") (pin "2") (pinfunction "S_2") (pintype "bidirectional"))
      (node (ref "R7") (pin "2") (pinfunction "2_2") (pintype "passive"))
    )
    (net (code "52") (name "RTS") (class "Default")
      (node (ref "IC3") (pin "19") (pinfunction "RTS_19") (pintype "bidirectional"))
      (node (ref "Q4") (pin "1") (pinfunction "E1_1") (pintype "bidirectional"))
      (node (ref "Q4") (pin "5") (pinfunction "B2_5") (pintype "bidirectional"))
    )
    (net (code "53") (name "RXD") (class "Default")
      (node (ref "IC2") (pin "34") (pinfunction "RXD0_34") (pintype "bidirectional"))
      (node (ref "R1") (pin "2") (pinfunction "2_2") (pintype "passive"))
    )
    (net (code "54") (name "TXD") (class "Default")
      (node (ref "IC2") (pin "35") (pinfunction "TXD0_35") (pintype "bidirectional"))
      (node (ref "R2") (pin "2") (pinfunction "2_2") (pintype "passive"))
    )
    (net (code "55") (name "VBATT") (class "Default")
      (node (ref "BATT_CONN") (pin "1") (pinfunction "2_1") (pintype "passive"))
      (node (ref "C2") (pin "1") (pinfunction "1_1") (pintype "passive"))
      (node (ref "C22") (pin "2") (pinfunction "2_2") (pintype "passive"))
      (node (ref "C6") (pin "1") (pinfunction "1_1") (pintype "passive"))
      (node (ref "D1") (pin "C") (pinfunction "C_C") (pintype "passive"))
      (node (ref "IC1") (pin "1") (pinfunction "IN_1") (pintype "input"))
      (node (ref "IC4") (pin "3") (pinfunction "VBAT_3") (pintype "bidirectional"))
      (node (ref "IC5") (pin "10") (pinfunction "BATT_10") (pintype "bidirectional"))
    )
    (net (code "56") (name "VCOM") (class "Default")
      (node (ref "C17") (pin "2") (pinfunction "2_2") (pintype "passive"))
      (node (ref "J1") (pin "24") (pinfunction "24_24") (pintype "passive"))
    )
    (net (code "57") (name "VUSB") (class "Default")
      (node (ref "C1") (pin "1") (pinfunction "1_1") (pintype "passive"))
      (node (ref "C8") (pin "1") (pinfunction "1_1") (pintype "passive"))
      (node (ref "D1") (pin "A") (pinfunction "A_A") (pintype "passive"))
      (node (ref "IC3") (pin "7") (pinfunction "REGIN_7") (pintype "bidirectional"))
      (node (ref "IC3") (pin "8") (pinfunction "VBUS_8") (pintype "bidirectional"))
      (node (ref "IC4") (pin "1") (pinfunction "CE_1") (pintype "input"))
      (node (ref "IC4") (pin "4") (pinfunction "VDD_4") (pintype "power_in"))
      (node (ref "J2") (pin "VBUS") (pinfunction "VBUS_VBUS") (pintype "power_in"))
    )
    (net (code "58") (name "unconnected-(IC2-NC-Pad32)") (class "Default")
      (node (ref "IC2") (pin "32") (pinfunction "NC_32") (pintype "no_connect"))
    )
    (net (code "59") (name "unconnected-(IC2-NC1-Pad27)") (class "Default")
      (node (ref "IC2") (pin "27") (pinfunction "NC1_27") (pintype "bidirectional"))
    )
    (net (code "60") (name "unconnected-(IC2-NC2-Pad28)") (class "Default")
      (node (ref "IC2") (pin "28") (pinfunction "NC2_28") (pintype "bidirectional"))
    )
    (net (code "61") (name "unconnected-(IC2-SCK{slash}CLK-Pad20)") (class "Default")
      (node (ref "IC2") (pin "20") (pinfunction "SCK/CLK_20") (pintype "bidirectional"))
    )
    (net (code "62") (name "unconnected-(IC2-SCS{slash}CMD-Pad19)") (class "Default")
      (node (ref "IC2") (pin "19") (pinfunction "SCS/CMD_19") (pintype "bidirectional"))
    )
    (net (code "63") (name "unconnected-(IC2-SDI{slash}SD1-Pad22)") (class "Default")
      (node (ref "IC2") (pin "22") (pinfunction "SDI/SD1_22") (pintype "bidirectional"))
    )
    (net (code "64") (name "unconnected-(IC2-SDO{slash}SD0-Pad21)") (class "Default")
      (node (ref "IC2") (pin "21") (pinfunction "SDO/SD0_21") (pintype "bidirectional"))
    )
    (net (code "65") (name "unconnected-(IC2-SHD{slash}SD2-Pad17)") (class "Default")
      (node (ref "IC2") (pin "17") (pinfunction "SHD/SD2_17") (pintype "bidirectional"))
    )
    (net (code "66") (name "unconnected-(IC2-SWP{slash}SD3-Pad18)") (class "Default")
      (node (ref "IC2") (pin "18") (pinfunction "SWP/SD3_18") (pintype "bidirectional"))
    )
    (net (code "67") (name "unconnected-(IC3-CTS-Pad18)") (class "Default")
      (node (ref "IC3") (pin "18") (pinfunction "CTS_18") (pintype "bidirectional"))
    )
    (net (code "68") (name "unconnected-(IC3-DCD-Pad24)") (class "Default")
      (node (ref "IC3") (pin "24") (pinfunction "DCD_24") (pintype "bidirectional"))
    )
    (net (code "69") (name "unconnected-(IC3-DSR-Pad22)") (class "Default")
      (node (ref "IC3") (pin "22") (pinfunction "DSR_22") (pintype "bidirectional"))
    )
    (net (code "70") (name "unconnected-(IC3-GPIO.0-Pad14)") (class "Default")
      (node (ref "IC3") (pin "14") (pinfunction "GPIO.0_14") (pintype "bidirectional"))
    )
    (net (code "71") (name "unconnected-(IC3-GPIO.1-Pad13)") (class "Default")
      (node (ref "IC3") (pin "13") (pinfunction "GPIO.1_13") (pintype "bidirectional"))
    )
    (net (code "72") (name "unconnected-(IC3-GPIO.2-Pad12)") (class "Default")
      (node (ref "IC3") (pin "12") (pinfunction "GPIO.2_12") (pintype "bidirectional"))
    )
    (net (code "73") (name "unconnected-(IC3-GPIO.3-Pad11)") (class "Default")
      (node (ref "IC3") (pin "11") (pinfunction "GPIO.3_11") (pintype "bidirectional"))
    )
    (net (code "74") (name "unconnected-(IC3-NC-Pad10)") (class "Default")
      (node (ref "IC3") (pin "10") (pinfunction "NC_10") (pintype "no_connect"))
    )
    (net (code "75") (name "unconnected-(IC3-RI-Pad1)") (class "Default")
      (node (ref "IC3") (pin "1") (pinfunction "RI_1") (pintype "bidirectional"))
    )
    (net (code "76") (name "unconnected-(IC3-SUSPEND-Pad17)") (class "Default")
      (node (ref "IC3") (pin "17") (pinfunction "SUSPEND_17") (pintype "bidirectional"))
    )
    (net (code "77") (name "unconnected-(IC3-~{RST}-Pad9)") (class "Default")
      (node (ref "IC3") (pin "9") (pinfunction "~{RST}_9") (pintype "bidirectional"))
    )
    (net (code "78") (name "unconnected-(IC3-~{SUSPEND}-Pad15)") (class "Default")
      (node (ref "IC3") (pin "15") (pinfunction "~{SUSPEND}_15") (pintype "bidirectional"))
    )
    (net (code "79") (name "unconnected-(IC5-AIN-Pad2)") (class "Default")
      (node (ref "IC5") (pin "2") (pinfunction "AIN_2") (pintype "bidirectional"))
    )
    (net (code "80") (name "unconnected-(IC5-ALRT-Pad8)") (class "Default")
      (node (ref "IC5") (pin "8") (pinfunction "ALRT_8") (pintype "bidirectional"))
    )
    (net (code "81") (name "unconnected-(IC5-N.C.-Pad1)") (class "Default")
      (node (ref "IC5") (pin "1") (pinfunction "N.C._1") (pintype "no_connect"))
    )
    (net (code "82") (name "unconnected-(IC5-THRM-Pad9)") (class "Default")
      (node (ref "IC5") (pin "9") (pinfunction "THRM_9") (pintype "bidirectional"))
    )
    (net (code "83") (name "unconnected-(IC6-32KHZ-Pad1)") (class "Default")
      (node (ref "IC6") (pin "1") (pinfunction "32KHZ_1") (pintype "output"))
    )
    (net (code "84") (name "unconnected-(IC6-NC-Pad5)") (class "Default")
      (node (ref "IC6") (pin "5") (pinfunction "NC_5") (pintype "no_connect"))
    )
    (net (code "85") (name "unconnected-(IC6-NC1-Pad6)") (class "Default")
      (node (ref "IC6") (pin "6") (pinfunction "NC1_6") (pintype "no_connect"))
    )
    (net (code "86") (name "unconnected-(IC6-NC2-Pad7)") (class "Default")
      (node (ref "IC6") (pin "7") (pinfunction "NC2_7") (pintype "no_connect"))
    )
    (net (code "87") (name "unconnected-(IC6-NC3-Pad8)") (class "Default")
      (node (ref "IC6") (pin "8") (pinfunction "NC3_8") (pintype "no_connect"))
    )
    (net (code "88") (name "unconnected-(IC6-NC4-Pad9)") (class "Default")
      (node (ref "IC6") (pin "9") (pinfunction "NC4_9") (pintype "no_connect"))
    )
    (net (code "89") (name "unconnected-(IC6-NC5-Pad10)") (class "Default")
      (node (ref "IC6") (pin "10") (pinfunction "NC5_10") (pintype "no_connect"))
    )
    (net (code "90") (name "unconnected-(IC6-NC6-Pad11)") (class "Default")
      (node (ref "IC6") (pin "11") (pinfunction "NC6_11") (pintype "no_connect"))
    )
    (net (code "91") (name "unconnected-(IC6-NC7-Pad12)") (class "Default")
      (node (ref "IC6") (pin "12") (pinfunction "NC7_12") (pintype "no_connect"))
    )
    (net (code "92") (name "unconnected-(IC6-{slash}RST-Pad4)") (class "Default")
      (node (ref "IC6") (pin "4") (pinfunction "/RST_4") (pintype "passive"))
    )
    (net (code "93") (name "unconnected-(J1-Pad1)") (class "Default")
      (node (ref "J1") (pin "1") (pinfunction "1_1") (pintype "passive"))
    )
    (net (code "94") (name "unconnected-(J1-Pad4)") (class "Default")
      (node (ref "J1") (pin "4") (pinfunction "4_4") (pintype "passive"))
    )
    (net (code "95") (name "unconnected-(J1-Pad6)") (class "Default")
      (node (ref "J1") (pin "6") (pinfunction "6_6") (pintype "passive"))
    )
    (net (code "96") (name "unconnected-(J1-Pad7)") (class "Default")
      (node (ref "J1") (pin "7") (pinfunction "7_7") (pintype "passive"))
    )
    (net (code "97") (name "unconnected-(J2-PadID)") (class "Default")
      (node (ref "J2") (pin "ID") (pinfunction "ID_ID") (pintype "bidirectional"))
    )
    (net (code "98") (name "unconnected-(U1-NC-Pad3)") (class "Default")
      (node (ref "U1") (pin "3") (pinfunction "NC_3") (pintype "bidirectional"))
    )
    (net (code "99") (name "unconnected-(U1-NC-Pad10)") (class "Default")
      (node (ref "U1") (pin "10") (pinfunction "NC_10") (pintype "bidirectional"))
    )
    (net (code "100") (name "unconnected-(U1-NC-Pad11)") (class "Default")
      (node (ref "U1") (pin "11") (pinfunction "NC_11") (pintype "bidirectional"))
    )
  )
)
